# tm-2.net
KiCad netlist of a schematic drawn in EAGLE
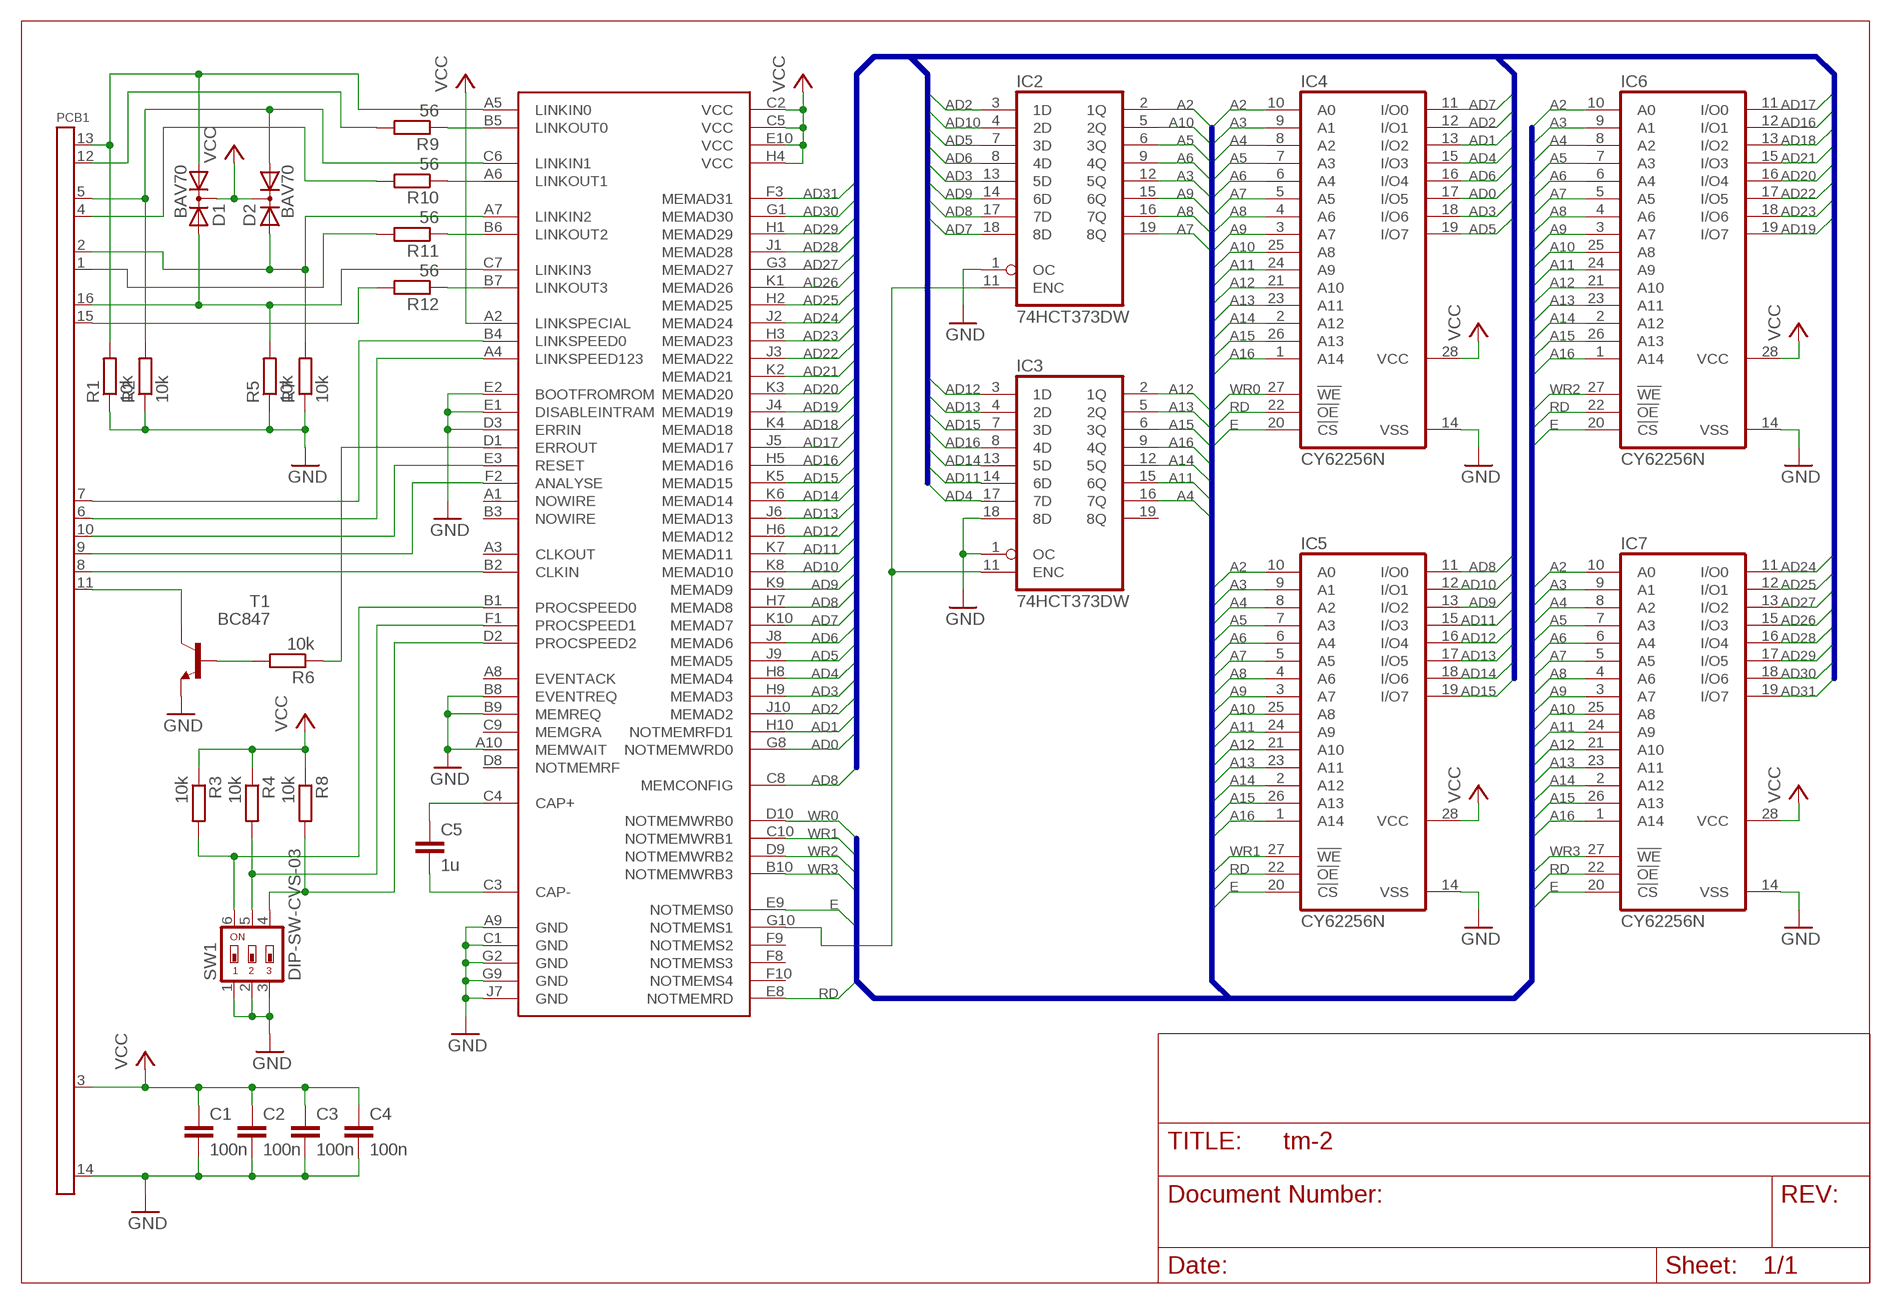
[diagram p0: schematic, sheet 1]

(export (version "E")
  (design (tool "Eeschema 10.0.6"))
  (components
    (comp (ref "C1")
      (value "100n")
      (footprint "eagle-import:C1206")
      (libsource (lib "eagle-import") (part "C-EUC1206"))
    )
    (comp (ref "C2")
      (value "100n")
      (footprint "eagle-import:C1206")
      (libsource (lib "eagle-import") (part "C-EUC1206"))
    )
    (comp (ref "C3")
      (value "100n")
      (footprint "eagle-import:C1206")
      (libsource (lib "eagle-import") (part "C-EUC1206"))
    )
    (comp (ref "C4")
      (value "100n")
      (footprint "eagle-import:C1206")
      (libsource (lib "eagle-import") (part "C-EUC1206"))
    )
    (comp (ref "C5")
      (value "1u")
      (footprint "eagle-import:C1206")
      (libsource (lib "eagle-import") (part "C-EUC1206"))
    )
    (comp (ref "D1")
      (value "BAV70")
      (footprint "eagle-import:SOT23")
      (libsource (lib "eagle-import") (part "DIODE-2AC|CASOT23"))
    )
    (comp (ref "D2")
      (value "BAV70")
      (footprint "eagle-import:SOT23")
      (libsource (lib "eagle-import") (part "DIODE-2AC|CASOT23"))
    )
    (comp (ref "IC1")
      (value "IMST800")
      (footprint "eagle-import:PGA84")
      (libsource (lib "eagle-import") (part "IMST800"))
    )
    (comp (ref "IC2")
      (value "74HCT373DW")
      (footprint "eagle-import:SO20W")
      (libsource (lib "eagle-import") (part "74373DWHCT"))
    )
    (comp (ref "IC3")
      (value "74HCT373DW")
      (footprint "eagle-import:SO20W")
      (libsource (lib "eagle-import") (part "74373DWHCT"))
    )
    (comp (ref "IC4")
      (value "CY62256N")
      (footprint "eagle-import:SOP28N")
      (libsource (lib "eagle-import") (part "CY62256N"))
    )
    (comp (ref "IC5")
      (value "CY62256N")
      (footprint "eagle-import:SOP28N")
      (libsource (lib "eagle-import") (part "CY62256N"))
    )
    (comp (ref "IC6")
      (value "CY62256N")
      (footprint "eagle-import:SOP28N")
      (libsource (lib "eagle-import") (part "CY62256N"))
    )
    (comp (ref "IC7")
      (value "CY62256N")
      (footprint "eagle-import:SOP28N")
      (libsource (lib "eagle-import") (part "CY62256N"))
    )
    (comp (ref "PCB1")
      (value "TRAM-1-PCB")
      (footprint "eagle-import:TRAM-1-PCB")
      (libsource (lib "eagle-import") (part "TRAM-1-PCB"))
    )
    (comp (ref "R1")
      (value "10k")
      (footprint "eagle-import:R1206")
      (libsource (lib "eagle-import") (part "R-EU_R1206"))
    )
    (comp (ref "R2")
      (value "10k")
      (footprint "eagle-import:R1206")
      (libsource (lib "eagle-import") (part "R-EU_R1206"))
    )
    (comp (ref "R3")
      (value "10k")
      (footprint "eagle-import:R1206")
      (libsource (lib "eagle-import") (part "R-EU_R1206"))
    )
    (comp (ref "R4")
      (value "10k")
      (footprint "eagle-import:R1206")
      (libsource (lib "eagle-import") (part "R-EU_R1206"))
    )
    (comp (ref "R5")
      (value "10k")
      (footprint "eagle-import:R1206")
      (libsource (lib "eagle-import") (part "R-EU_R1206"))
    )
    (comp (ref "R6")
      (value "10k")
      (footprint "eagle-import:R1206")
      (libsource (lib "eagle-import") (part "R-EU_R1206"))
    )
    (comp (ref "R7")
      (value "10k")
      (footprint "eagle-import:R1206")
      (libsource (lib "eagle-import") (part "R-EU_R1206"))
    )
    (comp (ref "R8")
      (value "10k")
      (footprint "eagle-import:R1206")
      (libsource (lib "eagle-import") (part "R-EU_R1206"))
    )
    (comp (ref "R9")
      (value "56")
      (footprint "eagle-import:R1206")
      (libsource (lib "eagle-import") (part "R-EU_R1206"))
    )
    (comp (ref "R10")
      (value "56")
      (footprint "eagle-import:R1206")
      (libsource (lib "eagle-import") (part "R-EU_R1206"))
    )
    (comp (ref "R11")
      (value "56")
      (footprint "eagle-import:R1206")
      (libsource (lib "eagle-import") (part "R-EU_R1206"))
    )
    (comp (ref "R12")
      (value "56")
      (footprint "eagle-import:R1206")
      (libsource (lib "eagle-import") (part "R-EU_R1206"))
    )
    (comp (ref "SW1")
      (value "DIP-SW-CVS-03")
      (footprint "eagle-import:DIP-SW-CVS-03")
      (libsource (lib "eagle-import") (part "DIP-SW-CVS-03"))
    )
    (comp (ref "T1")
      (value "BC847")
      (footprint "eagle-import:SOT23")
      (libsource (lib "eagle-import") (part "BC847"))
    )
  )
  (nets
    (net (code "1") (name "/A2") (class "Default")
      (node (ref "IC2") (pin "2") (pinfunction "1Q_2") (pintype "tri_state"))
      (node (ref "IC4") (pin "10") (pinfunction "A0_10") (pintype "input"))
      (node (ref "IC5") (pin "10") (pinfunction "A0_10") (pintype "input"))
      (node (ref "IC6") (pin "10") (pinfunction "A0_10") (pintype "input"))
      (node (ref "IC7") (pin "10") (pinfunction "A0_10") (pintype "input"))
    )
    (net (code "2") (name "/A3") (class "Default")
      (node (ref "IC2") (pin "12") (pinfunction "5Q_12") (pintype "tri_state"))
      (node (ref "IC4") (pin "9") (pinfunction "A1_9") (pintype "input"))
      (node (ref "IC5") (pin "9") (pinfunction "A1_9") (pintype "input"))
      (node (ref "IC6") (pin "9") (pinfunction "A1_9") (pintype "input"))
      (node (ref "IC7") (pin "9") (pinfunction "A1_9") (pintype "input"))
    )
    (net (code "3") (name "/A4") (class "Default")
      (node (ref "IC3") (pin "16") (pinfunction "7Q_16") (pintype "tri_state"))
      (node (ref "IC4") (pin "8") (pinfunction "A2_8") (pintype "input"))
      (node (ref "IC5") (pin "8") (pinfunction "A2_8") (pintype "input"))
      (node (ref "IC6") (pin "8") (pinfunction "A2_8") (pintype "input"))
      (node (ref "IC7") (pin "8") (pinfunction "A2_8") (pintype "input"))
    )
    (net (code "4") (name "/A5") (class "Default")
      (node (ref "IC2") (pin "6") (pinfunction "3Q_6") (pintype "tri_state"))
      (node (ref "IC4") (pin "7") (pinfunction "A3_7") (pintype "input"))
      (node (ref "IC5") (pin "7") (pinfunction "A3_7") (pintype "input"))
      (node (ref "IC6") (pin "7") (pinfunction "A3_7") (pintype "input"))
      (node (ref "IC7") (pin "7") (pinfunction "A3_7") (pintype "input"))
    )
    (net (code "5") (name "/A6") (class "Default")
      (node (ref "IC2") (pin "9") (pinfunction "4Q_9") (pintype "tri_state"))
      (node (ref "IC4") (pin "6") (pinfunction "A4_6") (pintype "input"))
      (node (ref "IC5") (pin "6") (pinfunction "A4_6") (pintype "input"))
      (node (ref "IC6") (pin "6") (pinfunction "A4_6") (pintype "input"))
      (node (ref "IC7") (pin "6") (pinfunction "A4_6") (pintype "input"))
    )
    (net (code "6") (name "/A7") (class "Default")
      (node (ref "IC2") (pin "19") (pinfunction "8Q_19") (pintype "tri_state"))
      (node (ref "IC4") (pin "5") (pinfunction "A5_5") (pintype "input"))
      (node (ref "IC5") (pin "5") (pinfunction "A5_5") (pintype "input"))
      (node (ref "IC6") (pin "5") (pinfunction "A5_5") (pintype "input"))
      (node (ref "IC7") (pin "5") (pinfunction "A5_5") (pintype "input"))
    )
    (net (code "7") (name "/A8") (class "Default")
      (node (ref "IC2") (pin "16") (pinfunction "7Q_16") (pintype "tri_state"))
      (node (ref "IC4") (pin "4") (pinfunction "A6_4") (pintype "input"))
      (node (ref "IC5") (pin "4") (pinfunction "A6_4") (pintype "input"))
      (node (ref "IC6") (pin "4") (pinfunction "A6_4") (pintype "input"))
      (node (ref "IC7") (pin "4") (pinfunction "A6_4") (pintype "input"))
    )
    (net (code "8") (name "/A9") (class "Default")
      (node (ref "IC2") (pin "15") (pinfunction "6Q_15") (pintype "tri_state"))
      (node (ref "IC4") (pin "3") (pinfunction "A7_3") (pintype "input"))
      (node (ref "IC5") (pin "3") (pinfunction "A7_3") (pintype "input"))
      (node (ref "IC6") (pin "3") (pinfunction "A7_3") (pintype "input"))
      (node (ref "IC7") (pin "3") (pinfunction "A7_3") (pintype "input"))
    )
    (net (code "9") (name "/A10") (class "Default")
      (node (ref "IC2") (pin "5") (pinfunction "2Q_5") (pintype "tri_state"))
      (node (ref "IC4") (pin "25") (pinfunction "A8_25") (pintype "input"))
      (node (ref "IC5") (pin "25") (pinfunction "A8_25") (pintype "input"))
      (node (ref "IC6") (pin "25") (pinfunction "A8_25") (pintype "input"))
      (node (ref "IC7") (pin "25") (pinfunction "A8_25") (pintype "input"))
    )
    (net (code "10") (name "/A11") (class "Default")
      (node (ref "IC3") (pin "15") (pinfunction "6Q_15") (pintype "tri_state"))
      (node (ref "IC4") (pin "24") (pinfunction "A9_24") (pintype "input"))
      (node (ref "IC5") (pin "24") (pinfunction "A9_24") (pintype "input"))
      (node (ref "IC6") (pin "24") (pinfunction "A9_24") (pintype "input"))
      (node (ref "IC7") (pin "24") (pinfunction "A9_24") (pintype "input"))
    )
    (net (code "11") (name "/A12") (class "Default")
      (node (ref "IC3") (pin "2") (pinfunction "1Q_2") (pintype "tri_state"))
      (node (ref "IC4") (pin "21") (pinfunction "A10_21") (pintype "input"))
      (node (ref "IC5") (pin "21") (pinfunction "A10_21") (pintype "input"))
      (node (ref "IC6") (pin "21") (pinfunction "A10_21") (pintype "input"))
      (node (ref "IC7") (pin "21") (pinfunction "A10_21") (pintype "input"))
    )
    (net (code "12") (name "/A13") (class "Default")
      (node (ref "IC3") (pin "5") (pinfunction "2Q_5") (pintype "tri_state"))
      (node (ref "IC4") (pin "23") (pinfunction "A11_23") (pintype "input"))
      (node (ref "IC5") (pin "23") (pinfunction "A11_23") (pintype "input"))
      (node (ref "IC6") (pin "23") (pinfunction "A11_23") (pintype "input"))
      (node (ref "IC7") (pin "23") (pinfunction "A11_23") (pintype "input"))
    )
    (net (code "13") (name "/A14") (class "Default")
      (node (ref "IC3") (pin "12") (pinfunction "5Q_12") (pintype "tri_state"))
      (node (ref "IC4") (pin "2") (pinfunction "A12_2") (pintype "input"))
      (node (ref "IC5") (pin "2") (pinfunction "A12_2") (pintype "input"))
      (node (ref "IC6") (pin "2") (pinfunction "A12_2") (pintype "input"))
      (node (ref "IC7") (pin "2") (pinfunction "A12_2") (pintype "input"))
    )
    (net (code "14") (name "/A15") (class "Default")
      (node (ref "IC3") (pin "6") (pinfunction "3Q_6") (pintype "tri_state"))
      (node (ref "IC4") (pin "26") (pinfunction "A13_26") (pintype "input"))
      (node (ref "IC5") (pin "26") (pinfunction "A13_26") (pintype "input"))
      (node (ref "IC6") (pin "26") (pinfunction "A13_26") (pintype "input"))
      (node (ref "IC7") (pin "26") (pinfunction "A13_26") (pintype "input"))
    )
    (net (code "15") (name "/A16") (class "Default")
      (node (ref "IC3") (pin "9") (pinfunction "4Q_9") (pintype "tri_state"))
      (node (ref "IC4") (pin "1") (pinfunction "A14_1") (pintype "input"))
      (node (ref "IC5") (pin "1") (pinfunction "A14_1") (pintype "input"))
      (node (ref "IC6") (pin "1") (pinfunction "A14_1") (pintype "input"))
      (node (ref "IC7") (pin "1") (pinfunction "A14_1") (pintype "input"))
    )
    (net (code "16") (name "/AD0") (class "Default")
      (node (ref "IC1") (pin "G8") (pinfunction "NOTMEMWRD0_G8") (pintype "output"))
      (node (ref "IC4") (pin "17") (pinfunction "I/O5_17") (pintype "bidirectional"))
    )
    (net (code "17") (name "/AD1") (class "Default")
      (node (ref "IC1") (pin "H10") (pinfunction "NOTMEMRFD1_H10") (pintype "output"))
      (node (ref "IC4") (pin "13") (pinfunction "I/O2_13") (pintype "bidirectional"))
    )
    (net (code "18") (name "/AD2") (class "Default")
      (node (ref "IC1") (pin "J10") (pinfunction "MEMAD2_J10") (pintype "output"))
      (node (ref "IC2") (pin "3") (pinfunction "1D_3") (pintype "input"))
      (node (ref "IC4") (pin "12") (pinfunction "I/O1_12") (pintype "bidirectional"))
    )
    (net (code "19") (name "/AD3") (class "Default")
      (node (ref "IC1") (pin "H9") (pinfunction "MEMAD3_H9") (pintype "output"))
      (node (ref "IC2") (pin "13") (pinfunction "5D_13") (pintype "input"))
      (node (ref "IC4") (pin "18") (pinfunction "I/O6_18") (pintype "bidirectional"))
    )
    (net (code "20") (name "/AD4") (class "Default")
      (node (ref "IC1") (pin "H8") (pinfunction "MEMAD4_H8") (pintype "output"))
      (node (ref "IC3") (pin "17") (pinfunction "7D_17") (pintype "input"))
      (node (ref "IC4") (pin "15") (pinfunction "I/O3_15") (pintype "bidirectional"))
    )
    (net (code "21") (name "/AD5") (class "Default")
      (node (ref "IC1") (pin "J9") (pinfunction "MEMAD5_J9") (pintype "output"))
      (node (ref "IC2") (pin "7") (pinfunction "3D_7") (pintype "input"))
      (node (ref "IC4") (pin "19") (pinfunction "I/O7_19") (pintype "bidirectional"))
    )
    (net (code "22") (name "/AD6") (class "Default")
      (node (ref "IC1") (pin "J8") (pinfunction "MEMAD6_J8") (pintype "output"))
      (node (ref "IC2") (pin "8") (pinfunction "4D_8") (pintype "input"))
      (node (ref "IC4") (pin "16") (pinfunction "I/O4_16") (pintype "bidirectional"))
    )
    (net (code "23") (name "/AD7") (class "Default")
      (node (ref "IC1") (pin "K10") (pinfunction "MEMAD7_K10") (pintype "output"))
      (node (ref "IC2") (pin "18") (pinfunction "8D_18") (pintype "input"))
      (node (ref "IC4") (pin "11") (pinfunction "I/O0_11") (pintype "bidirectional"))
    )
    (net (code "24") (name "/AD8") (class "Default")
      (node (ref "IC1") (pin "C8") (pinfunction "MEMCONFIG_C8") (pintype "input"))
      (node (ref "IC1") (pin "H7") (pinfunction "MEMAD8_H7") (pintype "output"))
      (node (ref "IC2") (pin "17") (pinfunction "7D_17") (pintype "input"))
      (node (ref "IC5") (pin "11") (pinfunction "I/O0_11") (pintype "bidirectional"))
    )
    (net (code "25") (name "/AD9") (class "Default")
      (node (ref "IC1") (pin "K9") (pinfunction "MEMAD9_K9") (pintype "output"))
      (node (ref "IC2") (pin "14") (pinfunction "6D_14") (pintype "input"))
      (node (ref "IC5") (pin "13") (pinfunction "I/O2_13") (pintype "bidirectional"))
    )
    (net (code "26") (name "/AD10") (class "Default")
      (node (ref "IC1") (pin "K8") (pinfunction "MEMAD10_K8") (pintype "output"))
      (node (ref "IC2") (pin "4") (pinfunction "2D_4") (pintype "input"))
      (node (ref "IC5") (pin "12") (pinfunction "I/O1_12") (pintype "bidirectional"))
    )
    (net (code "27") (name "/AD11") (class "Default")
      (node (ref "IC1") (pin "K7") (pinfunction "MEMAD11_K7") (pintype "output"))
      (node (ref "IC3") (pin "14") (pinfunction "6D_14") (pintype "input"))
      (node (ref "IC5") (pin "15") (pinfunction "I/O3_15") (pintype "bidirectional"))
    )
    (net (code "28") (name "/AD12") (class "Default")
      (node (ref "IC1") (pin "H6") (pinfunction "MEMAD12_H6") (pintype "output"))
      (node (ref "IC3") (pin "3") (pinfunction "1D_3") (pintype "input"))
      (node (ref "IC5") (pin "16") (pinfunction "I/O4_16") (pintype "bidirectional"))
    )
    (net (code "29") (name "/AD13") (class "Default")
      (node (ref "IC1") (pin "J6") (pinfunction "MEMAD13_J6") (pintype "output"))
      (node (ref "IC3") (pin "4") (pinfunction "2D_4") (pintype "input"))
      (node (ref "IC5") (pin "17") (pinfunction "I/O5_17") (pintype "bidirectional"))
    )
    (net (code "30") (name "/AD14") (class "Default")
      (node (ref "IC1") (pin "K6") (pinfunction "MEMAD14_K6") (pintype "output"))
      (node (ref "IC3") (pin "13") (pinfunction "5D_13") (pintype "input"))
      (node (ref "IC5") (pin "18") (pinfunction "I/O6_18") (pintype "bidirectional"))
    )
    (net (code "31") (name "/AD15") (class "Default")
      (node (ref "IC1") (pin "K5") (pinfunction "MEMAD15_K5") (pintype "output"))
      (node (ref "IC3") (pin "7") (pinfunction "3D_7") (pintype "input"))
      (node (ref "IC5") (pin "19") (pinfunction "I/O7_19") (pintype "bidirectional"))
    )
    (net (code "32") (name "/AD16") (class "Default")
      (node (ref "IC1") (pin "H5") (pinfunction "MEMAD16_H5") (pintype "output"))
      (node (ref "IC3") (pin "8") (pinfunction "4D_8") (pintype "input"))
      (node (ref "IC6") (pin "12") (pinfunction "I/O1_12") (pintype "bidirectional"))
    )
    (net (code "33") (name "/AD17") (class "Default")
      (node (ref "IC1") (pin "J5") (pinfunction "MEMAD17_J5") (pintype "output"))
      (node (ref "IC6") (pin "11") (pinfunction "I/O0_11") (pintype "bidirectional"))
    )
    (net (code "34") (name "/AD18") (class "Default")
      (node (ref "IC1") (pin "K4") (pinfunction "MEMAD18_K4") (pintype "output"))
      (node (ref "IC6") (pin "13") (pinfunction "I/O2_13") (pintype "bidirectional"))
    )
    (net (code "35") (name "/AD19") (class "Default")
      (node (ref "IC1") (pin "J4") (pinfunction "MEMAD19_J4") (pintype "output"))
      (node (ref "IC6") (pin "19") (pinfunction "I/O7_19") (pintype "bidirectional"))
    )
    (net (code "36") (name "/AD20") (class "Default")
      (node (ref "IC1") (pin "K3") (pinfunction "MEMAD20_K3") (pintype "output"))
      (node (ref "IC6") (pin "16") (pinfunction "I/O4_16") (pintype "bidirectional"))
    )
    (net (code "37") (name "/AD21") (class "Default")
      (node (ref "IC1") (pin "K2") (pinfunction "MEMAD21_K2") (pintype "output"))
      (node (ref "IC6") (pin "15") (pinfunction "I/O3_15") (pintype "bidirectional"))
    )
    (net (code "38") (name "/AD22") (class "Default")
      (node (ref "IC1") (pin "J3") (pinfunction "MEMAD22_J3") (pintype "output"))
      (node (ref "IC6") (pin "17") (pinfunction "I/O5_17") (pintype "bidirectional"))
    )
    (net (code "39") (name "/AD23") (class "Default")
      (node (ref "IC1") (pin "H3") (pinfunction "MEMAD23_H3") (pintype "output"))
      (node (ref "IC6") (pin "18") (pinfunction "I/O6_18") (pintype "bidirectional"))
    )
    (net (code "40") (name "/AD24") (class "Default")
      (node (ref "IC1") (pin "J2") (pinfunction "MEMAD24_J2") (pintype "output"))
      (node (ref "IC7") (pin "11") (pinfunction "I/O0_11") (pintype "bidirectional"))
    )
    (net (code "41") (name "/AD25") (class "Default")
      (node (ref "IC1") (pin "H2") (pinfunction "MEMAD25_H2") (pintype "output"))
      (node (ref "IC7") (pin "12") (pinfunction "I/O1_12") (pintype "bidirectional"))
    )
    (net (code "42") (name "/AD26") (class "Default")
      (node (ref "IC1") (pin "K1") (pinfunction "MEMAD26_K1") (pintype "output"))
      (node (ref "IC7") (pin "15") (pinfunction "I/O3_15") (pintype "bidirectional"))
    )
    (net (code "43") (name "/AD27") (class "Default")
      (node (ref "IC1") (pin "G3") (pinfunction "MEMAD27_G3") (pintype "output"))
      (node (ref "IC7") (pin "13") (pinfunction "I/O2_13") (pintype "bidirectional"))
    )
    (net (code "44") (name "/AD28") (class "Default")
      (node (ref "IC1") (pin "J1") (pinfunction "MEMAD28_J1") (pintype "output"))
      (node (ref "IC7") (pin "16") (pinfunction "I/O4_16") (pintype "bidirectional"))
    )
    (net (code "45") (name "/AD29") (class "Default")
      (node (ref "IC1") (pin "H1") (pinfunction "MEMAD29_H1") (pintype "output"))
      (node (ref "IC7") (pin "17") (pinfunction "I/O5_17") (pintype "bidirectional"))
    )
    (net (code "46") (name "/AD30") (class "Default")
      (node (ref "IC1") (pin "G1") (pinfunction "MEMAD30_G1") (pintype "output"))
      (node (ref "IC7") (pin "18") (pinfunction "I/O6_18") (pintype "bidirectional"))
    )
    (net (code "47") (name "/AD31") (class "Default")
      (node (ref "IC1") (pin "F3") (pinfunction "MEMAD31_F3") (pintype "output"))
      (node (ref "IC7") (pin "19") (pinfunction "I/O7_19") (pintype "bidirectional"))
    )
    (net (code "48") (name "/E") (class "Default")
      (node (ref "IC1") (pin "E9") (pinfunction "NOTMEMS0_E9") (pintype "output"))
      (node (ref "IC4") (pin "20") (pinfunction "~{CS}_20") (pintype "input"))
      (node (ref "IC5") (pin "20") (pinfunction "~{CS}_20") (pintype "input"))
      (node (ref "IC6") (pin "20") (pinfunction "~{CS}_20") (pintype "input"))
      (node (ref "IC7") (pin "20") (pinfunction "~{CS}_20") (pintype "input"))
    )
    (net (code "49") (name "/RD") (class "Default")
      (node (ref "IC1") (pin "E8") (pinfunction "NOTMEMRD_E8") (pintype "output"))
      (node (ref "IC4") (pin "22") (pinfunction "~{OE}_22") (pintype "input"))
      (node (ref "IC5") (pin "22") (pinfunction "~{OE}_22") (pintype "input"))
      (node (ref "IC6") (pin "22") (pinfunction "~{OE}_22") (pintype "input"))
      (node (ref "IC7") (pin "22") (pinfunction "~{OE}_22") (pintype "input"))
    )
    (net (code "50") (name "/WR0") (class "Default")
      (node (ref "IC1") (pin "D10") (pinfunction "NOTMEMWRB0_D10") (pintype "output"))
      (node (ref "IC4") (pin "27") (pinfunction "~{WE}_27") (pintype "input"))
    )
    (net (code "51") (name "/WR1") (class "Default")
      (node (ref "IC1") (pin "C10") (pinfunction "NOTMEMWRB1_C10") (pintype "output"))
      (node (ref "IC5") (pin "27") (pinfunction "~{WE}_27") (pintype "input"))
    )
    (net (code "52") (name "/WR2") (class "Default")
      (node (ref "IC1") (pin "D9") (pinfunction "NOTMEMWRB2_D9") (pintype "output"))
      (node (ref "IC6") (pin "27") (pinfunction "~{WE}_27") (pintype "input"))
    )
    (net (code "53") (name "/WR3") (class "Default")
      (node (ref "IC1") (pin "B10") (pinfunction "NOTMEMWRB3_B10") (pintype "output"))
      (node (ref "IC7") (pin "27") (pinfunction "~{WE}_27") (pintype "input"))
    )
    (net (code "54") (name "GND") (class "Default")
      (node (ref "C1") (pin "2") (pinfunction "2_2") (pintype "passive"))
      (node (ref "C2") (pin "2") (pinfunction "2_2") (pintype "passive"))
      (node (ref "C3") (pin "2") (pinfunction "2_2") (pintype "passive"))
      (node (ref "C4") (pin "2") (pinfunction "2_2") (pintype "passive"))
      (node (ref "IC1") (pin "A10") (pinfunction "MEMWAIT_A10") (pintype "input"))
      (node (ref "IC1") (pin "A9") (pinfunction "GND_A9") (pintype "power_in"))
      (node (ref "IC1") (pin "B8") (pinfunction "EVENTREQ_B8") (pintype "input"))
      (node (ref "IC1") (pin "B9") (pinfunction "MEMREQ_B9") (pintype "input"))
      (node (ref "IC1") (pin "C1") (pinfunction "GND_C1") (pintype "power_in"))
      (node (ref "IC1") (pin "D3") (pinfunction "ERRIN_D3") (pintype "input"))
      (node (ref "IC1") (pin "E1") (pinfunction "DISABLEINTRAM_E1") (pintype "input"))
      (node (ref "IC1") (pin "E2") (pinfunction "BOOTFROMROM_E2") (pintype "input"))
      (node (ref "IC1") (pin "G2") (pinfunction "GND_G2") (pintype "power_in"))
      (node (ref "IC1") (pin "G9") (pinfunction "GND_G9") (pintype "power_in"))
      (node (ref "IC1") (pin "J7") (pinfunction "GND_J7") (pintype "power_in"))
      (node (ref "IC2") (pin "1") (pinfunction "OC_1") (pintype "input"))
      (node (ref "IC3") (pin "1") (pinfunction "OC_1") (pintype "input"))
      (node (ref "IC3") (pin "18") (pinfunction "8D_18") (pintype "input"))
      (node (ref "IC4") (pin "14") (pinfunction "VSS_14") (pintype "power_in"))
      (node (ref "IC5") (pin "14") (pinfunction "VSS_14") (pintype "power_in"))
      (node (ref "IC6") (pin "14") (pinfunction "VSS_14") (pintype "power_in"))
      (node (ref "IC7") (pin "14") (pinfunction "VSS_14") (pintype "power_in"))
      (node (ref "PCB1") (pin "14") (pinfunction "GND_14") (pintype "passive"))
      (node (ref "R1") (pin "1") (pinfunction "1_1") (pintype "passive"))
      (node (ref "R2") (pin "1") (pinfunction "1_1") (pintype "passive"))
      (node (ref "R5") (pin "1") (pinfunction "1_1") (pintype "passive"))
      (node (ref "R7") (pin "1") (pinfunction "1_1") (pintype "passive"))
      (node (ref "SW1") (pin "1") (pinfunction "1_1") (pintype "passive"))
      (node (ref "SW1") (pin "2") (pinfunction "2_2") (pintype "passive"))
      (node (ref "SW1") (pin "3") (pinfunction "3_3") (pintype "passive"))
      (node (ref "T1") (pin "2") (pinfunction "E_2") (pintype "passive"))
    )
    (net (code "55") (name "Net-(D1-A1)") (class "Default")
      (node (ref "D1") (pin "1") (pinfunction "A1_1") (pintype "passive"))
      (node (ref "IC1") (pin "A5") (pinfunction "LINKIN0_A5") (pintype "input"))
      (node (ref "PCB1") (pin "13") (pinfunction "LINK0IN_13") (pintype "passive"))
      (node (ref "R1") (pin "2") (pinfunction "2_2") (pintype "passive"))
    )
    (net (code "56") (name "Net-(D1-A2)") (class "Default")
      (node (ref "D1") (pin "2") (pinfunction "A2_2") (pintype "passive"))
      (node (ref "IC1") (pin "C7") (pinfunction "LINKIN3_C7") (pintype "input"))
      (node (ref "PCB1") (pin "16") (pinfunction "LINK3IN_16") (pintype "passive"))
      (node (ref "R5") (pin "2") (pinfunction "2_2") (pintype "passive"))
    )
    (net (code "57") (name "Net-(D2-A1)") (class "Default")
      (node (ref "D2") (pin "1") (pinfunction "A1_1") (pintype "passive"))
      (node (ref "IC1") (pin "C6") (pinfunction "LINKIN1_C6") (pintype "input"))
      (node (ref "PCB1") (pin "5") (pinfunction "LINK1IN_5") (pintype "passive"))
      (node (ref "R2") (pin "2") (pinfunction "2_2") (pintype "passive"))
    )
    (net (code "58") (name "Net-(D2-A2)") (class "Default")
      (node (ref "D2") (pin "2") (pinfunction "A2_2") (pintype "passive"))
      (node (ref "IC1") (pin "A7") (pinfunction "LINKIN2_A7") (pintype "input"))
      (node (ref "PCB1") (pin "2") (pinfunction "LINK2IN_2") (pintype "passive"))
      (node (ref "R7") (pin "2") (pinfunction "2_2") (pintype "passive"))
    )
    (net (code "59") (name "Net-(IC1-ANALYSE)") (class "Default")
      (node (ref "IC1") (pin "F2") (pinfunction "ANALYSE_F2") (pintype "input"))
      (node (ref "PCB1") (pin "9") (pinfunction "ANALYSE_9") (pintype "passive"))
    )
    (net (code "60") (name "Net-(IC1-CAP+)") (class "Default")
      (node (ref "C5") (pin "1") (pinfunction "1_1") (pintype "passive"))
      (node (ref "IC1") (pin "C4") (pinfunction "CAP+_C4") (pintype "passive"))
    )
    (net (code "61") (name "Net-(IC1-CAP-)") (class "Default")
      (node (ref "C5") (pin "2") (pinfunction "2_2") (pintype "passive"))
      (node (ref "IC1") (pin "C3") (pinfunction "CAP-_C3") (pintype "passive"))
    )
    (net (code "62") (name "Net-(IC1-CLKIN)") (class "Default")
      (node (ref "IC1") (pin "B2") (pinfunction "CLKIN_B2") (pintype "input"))
      (node (ref "PCB1") (pin "8") (pinfunction "CLOCKIN_8") (pintype "passive"))
    )
    (net (code "63") (name "Net-(IC1-ERROUT)") (class "Default")
      (node (ref "IC1") (pin "D1") (pinfunction "ERROUT_D1") (pintype "output"))
      (node (ref "R6") (pin "1") (pinfunction "1_1") (pintype "passive"))
    )
    (net (code "64") (name "Net-(IC1-LINKOUT0)") (class "Default")
      (node (ref "IC1") (pin "B5") (pinfunction "LINKOUT0_B5") (pintype "output"))
      (node (ref "R9") (pin "1") (pinfunction "1_1") (pintype "passive"))
    )
    (net (code "65") (name "Net-(IC1-LINKOUT1)") (class "Default")
      (node (ref "IC1") (pin "A6") (pinfunction "LINKOUT1_A6") (pintype "output"))
      (node (ref "R10") (pin "1") (pinfunction "1_1") (pintype "passive"))
    )
    (net (code "66") (name "Net-(IC1-LINKOUT2)") (class "Default")
      (node (ref "IC1") (pin "B6") (pinfunction "LINKOUT2_B6") (pintype "output"))
      (node (ref "R11") (pin "1") (pinfunction "1_1") (pintype "passive"))
    )
    (net (code "67") (name "Net-(IC1-LINKOUT3)") (class "Default")
      (node (ref "IC1") (pin "B7") (pinfunction "LINKOUT3_B7") (pintype "output"))
      (node (ref "R12") (pin "1") (pinfunction "1_1") (pintype "passive"))
    )
    (net (code "68") (name "Net-(IC1-LINKSPEED0)") (class "Default")
      (node (ref "IC1") (pin "B4") (pinfunction "LINKSPEED0_B4") (pintype "input"))
      (node (ref "PCB1") (pin "7") (pinfunction "LINKSPEEDB_7") (pintype "passive"))
    )
    (net (code "69") (name "Net-(IC1-LINKSPEED123)") (class "Default")
      (node (ref "IC1") (pin "A4") (pinfunction "LINKSPEED123_A4") (pintype "input"))
      (node (ref "PCB1") (pin "6") (pinfunction "LINKSPEEDA_6") (pintype "passive"))
    )
    (net (code "70") (name "Net-(IC1-NOTMEMS1)") (class "Default")
      (node (ref "IC1") (pin "G10") (pinfunction "NOTMEMS1_G10") (pintype "output"))
      (node (ref "IC2") (pin "11") (pinfunction "ENC_11") (pintype "input"))
      (node (ref "IC3") (pin "11") (pinfunction "ENC_11") (pintype "input"))
    )
    (net (code "71") (name "Net-(IC1-PROCSPEED0)") (class "Default")
      (node (ref "IC1") (pin "B1") (pinfunction "PROCSPEED0_B1") (pintype "input"))
      (node (ref "R3") (pin "2") (pinfunction "2_2") (pintype "passive"))
      (node (ref "SW1") (pin "6") (pinfunction "6_6") (pintype "passive"))
    )
    (net (code "72") (name "Net-(IC1-PROCSPEED1)") (class "Default")
      (node (ref "IC1") (pin "F1") (pinfunction "PROCSPEED1_F1") (pintype "input"))
      (node (ref "R4") (pin "2") (pinfunction "2_2") (pintype "passive"))
      (node (ref "SW1") (pin "5") (pinfunction "5_5") (pintype "passive"))
    )
    (net (code "73") (name "Net-(IC1-PROCSPEED2)") (class "Default")
      (node (ref "IC1") (pin "D2") (pinfunction "PROCSPEED2_D2") (pintype "input"))
      (node (ref "R8") (pin "2") (pinfunction "2_2") (pintype "passive"))
      (node (ref "SW1") (pin "4") (pinfunction "4_4") (pintype "passive"))
    )
    (net (code "74") (name "Net-(IC1-RESET)") (class "Default")
      (node (ref "IC1") (pin "E3") (pinfunction "RESET_E3") (pintype "input"))
      (node (ref "PCB1") (pin "10") (pinfunction "RESET_10") (pintype "passive"))
    )
    (net (code "75") (name "Net-(PCB1-LINK0OUT)") (class "Default")
      (node (ref "PCB1") (pin "12") (pinfunction "LINK0OUT_12") (pintype "passive"))
      (node (ref "R9") (pin "2") (pinfunction "2_2") (pintype "passive"))
    )
    (net (code "76") (name "Net-(PCB1-LINK1OUT)") (class "Default")
      (node (ref "PCB1") (pin "4") (pinfunction "LINK1OUT_4") (pintype "passive"))
      (node (ref "R10") (pin "2") (pinfunction "2_2") (pintype "passive"))
    )
    (net (code "77") (name "Net-(PCB1-LINK2OUT)") (class "Default")
      (node (ref "PCB1") (pin "1") (pinfunction "LINK2OUT_1") (pintype "passive"))
      (node (ref "R11") (pin "2") (pinfunction "2_2") (pintype "passive"))
    )
    (net (code "78") (name "Net-(PCB1-LINK3OUT)") (class "Default")
      (node (ref "PCB1") (pin "15") (pinfunction "LINK3OUT_15") (pintype "passive"))
      (node (ref "R12") (pin "2") (pinfunction "2_2") (pintype "passive"))
    )
    (net (code "79") (name "Net-(PCB1-NOTERROR)") (class "Default")
      (node (ref "PCB1") (pin "11") (pinfunction "NOTERROR_11") (pintype "passive"))
      (node (ref "T1") (pin "3") (pinfunction "C_3") (pintype "passive"))
    )
    (net (code "80") (name "Net-(T1-B)") (class "Default")
      (node (ref "R6") (pin "2") (pinfunction "2_2") (pintype "passive"))
      (node (ref "T1") (pin "1") (pinfunction "B_1") (pintype "passive"))
    )
    (net (code "81") (name "VCC") (class "Default")
      (node (ref "C1") (pin "1") (pinfunction "1_1") (pintype "passive"))
      (node (ref "C2") (pin "1") (pinfunction "1_1") (pintype "passive"))
      (node (ref "C3") (pin "1") (pinfunction "1_1") (pintype "passive"))
      (node (ref "C4") (pin "1") (pinfunction "1_1") (pintype "passive"))
      (node (ref "D1") (pin "3") (pinfunction "C_3") (pintype "passive"))
      (node (ref "D2") (pin "3") (pinfunction "C_3") (pintype "passive"))
      (node (ref "IC1") (pin "A2") (pinfunction "LINKSPECIAL_A2") (pintype "input"))
      (node (ref "IC1") (pin "C2") (pinfunction "VCC_C2") (pintype "power_in"))
      (node (ref "IC1") (pin "C5") (pinfunction "VCC_C5") (pintype "power_in"))
      (node (ref "IC1") (pin "E10") (pinfunction "VCC_E10") (pintype "power_in"))
      (node (ref "IC1") (pin "H4") (pinfunction "VCC_H4") (pintype "power_in"))
      (node (ref "IC4") (pin "28") (pinfunction "VCC_28") (pintype "power_in"))
      (node (ref "IC5") (pin "28") (pinfunction "VCC_28") (pintype "power_in"))
      (node (ref "IC6") (pin "28") (pinfunction "VCC_28") (pintype "power_in"))
      (node (ref "IC7") (pin "28") (pinfunction "VCC_28") (pintype "power_in"))
      (node (ref "PCB1") (pin "3") (pinfunction "VCC_3") (pintype "passive"))
      (node (ref "R3") (pin "1") (pinfunction "1_1") (pintype "passive"))
      (node (ref "R4") (pin "1") (pinfunction "1_1") (pintype "passive"))
      (node (ref "R8") (pin "1") (pinfunction "1_1") (pintype "passive"))
    )
    (net (code "82") (name "unconnected-(IC1-CLKOUT-PadA3)") (class "Default")
      (node (ref "IC1") (pin "A3") (pinfunction "CLKOUT_A3") (pintype "output"))
    )
    (net (code "83") (name "unconnected-(IC1-EVENTACK-PadA8)") (class "Default")
      (node (ref "IC1") (pin "A8") (pinfunction "EVENTACK_A8") (pintype "output"))
    )
    (net (code "84") (name "unconnected-(IC1-MEMGRA-PadC9)") (class "Default")
      (node (ref "IC1") (pin "C9") (pinfunction "MEMGRA_C9") (pintype "output"))
    )
    (net (code "85") (name "unconnected-(IC1-NOTMEMRF-PadD8)") (class "Default")
      (node (ref "IC1") (pin "D8") (pinfunction "NOTMEMRF_D8") (pintype "output"))
    )
    (net (code "86") (name "unconnected-(IC1-NOTMEMS2-PadF9)") (class "Default")
      (node (ref "IC1") (pin "F9") (pinfunction "NOTMEMS2_F9") (pintype "output"))
    )
    (net (code "87") (name "unconnected-(IC1-NOTMEMS3-PadF8)") (class "Default")
      (node (ref "IC1") (pin "F8") (pinfunction "NOTMEMS3_F8") (pintype "output"))
    )
    (net (code "88") (name "unconnected-(IC1-NOTMEMS4-PadF10)") (class "Default")
      (node (ref "IC1") (pin "F10") (pinfunction "NOTMEMS4_F10") (pintype "output"))
    )
    (net (code "89") (name "unconnected-(IC1-NOWIRE-PadA1)") (class "Default")
      (node (ref "IC1") (pin "A1") (pinfunction "NOWIRE_A1") (pintype "no_connect"))
    )
    (net (code "90") (name "unconnected-(IC1-NOWIRE-PadB3)") (class "Default")
      (node (ref "IC1") (pin "B3") (pinfunction "NOWIRE_B3") (pintype "no_connect"))
    )
    (net (code "91") (name "unconnected-(IC3A-8Q-Pad19)") (class "Default")
      (node (ref "IC3") (pin "19") (pinfunction "8Q_19") (pintype "tri_state"))
    )
  )
)
